# 5V_BUCK.net
KiCad netlist of a schematic drawn in Altium Designer
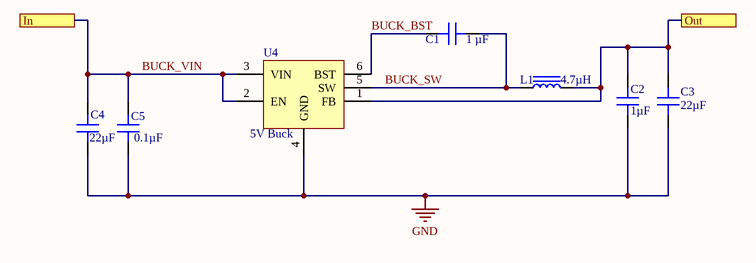
[diagram p0: 5V_BUCK.SchDoc]

(export (version "E")
  (design (tool "Eeschema 10.0.6"))
  (components
    (comp (ref "C1")
      (value "1 µF")
      (footprint "CAP 0402_1005")
      (description "CAP CER 0.1UF 16V X7R 0402")
      (fields (field (name "PART NUMBER") "C0402C104K4RACAUTO") (field (name "MANUFACTURER") "KEMET"))
      (libsource (lib "Celestial Altium Library - altium_library") (part "Capacitor"))
    )
    (comp (ref "C2")
      (value "1µF")
      (footprint "CAP 0603_1608")
      (description "CAP CER 1UF 25V X7R 0603")
      (fields
        (field (name "PART NUMBER") "GCJ188R71E105KA01D")
        (field (name "MANUFACTURER") "Murata Electronics")
      )
      (libsource (lib "Celestial Altium Library - altium_library") (part "Capacitor"))
    )
    (comp (ref "C3")
      (value "22µF")
      (footprint "CAP 0805_2012")
      (description "CAP CER 22UF 16V X5R 0805")
      (fields
        (field (name "PART NUMBER") "CL21A226MOQNNNE")
        (field (name "MANUFACTURER") "Samsung Electro-Mechanics")
      )
      (libsource (lib "Celestial Altium Library - altium_library") (part "Capacitor"))
    )
    (comp (ref "C4")
      (value "22µF")
      (footprint "CAP 0805_2012")
      (description "CAP CER 10UF 25V X7S 0805")
      (fields
        (field (name "PART NUMBER") "C2012X7S1E106K125AC")
        (field (name "MANUFACTURER") "TDK Corporation")
      )
      (libsource (lib "Celestial Altium Library - altium_library") (part "Capacitor"))
    )
    (comp (ref "C5")
      (value "0.1µF")
      (footprint "CAP 0603_1608")
      (description "CAP CER 0.1UF 100V 0603 EPOXY")
      (fields
        (field (name "PART NUMBER") "GCG188R92A104KA03D")
        (field (name "MANUFACTURER") "Murata Electronics")
      )
      (libsource (lib "Celestial Altium Library - altium_library") (part "Capacitor"))
    )
    (comp (ref "L1")
      (value "4.7µH")
      (footprint "IND 1008_2520")
      (description "FIXED IND 4.7UH 1A 110 MOHM SMD")
      (fields (field (name "PART NUMBER") "MLP2520S4R7ST0S1") (field (name "MANUFACTURER") "TDK Corporation"))
      (libsource (lib "Celestial Altium Library - altium_library") (part "Inductor"))
    )
    (comp (ref "U4")
      (value "5V Buck")
      (footprint "TSOT-26-6 - 3.2mm")
      (description "5V fixed step down Buck")
      (libsource (lib "IC") (part "AP63205WU-7"))
    )
  )
  (nets
    (net (code "1") (name "/BUCK_BST") (class "Default")
      (node (ref "C1") (pin "1") (pinfunction "1_1") (pintype "passive"))
      (node (ref "U4") (pin "6") (pinfunction "BST_6") (pintype "passive"))
    )
    (net (code "2") (name "/BUCK_SW") (class "Default")
      (node (ref "C1") (pin "2") (pinfunction "2_2") (pintype "passive"))
      (node (ref "L1") (pin "1") (pinfunction "1_1") (pintype "passive"))
      (node (ref "U4") (pin "5") (pinfunction "SW_5") (pintype "passive"))
    )
    (net (code "3") (name "/BUCK_VIN") (class "Default")
      (node (ref "C4") (pin "2") (pinfunction "2_2") (pintype "passive"))
      (node (ref "C5") (pin "1") (pinfunction "1_1") (pintype "passive"))
      (node (ref "U4") (pin "2") (pinfunction "EN_2") (pintype "passive"))
      (node (ref "U4") (pin "3") (pinfunction "VIN_3") (pintype "passive"))
    )
    (net (code "4") (name "/Out") (class "Default")
      (node (ref "C2") (pin "2") (pinfunction "2_2") (pintype "passive"))
      (node (ref "C3") (pin "2") (pinfunction "2_2") (pintype "passive"))
      (node (ref "L1") (pin "2") (pinfunction "2_2") (pintype "passive"))
      (node (ref "U4") (pin "1") (pinfunction "FB_1") (pintype "passive"))
    )
    (net (code "5") (name "GND") (class "Default")
      (node (ref "C2") (pin "1") (pinfunction "1_1") (pintype "passive"))
      (node (ref "C3") (pin "1") (pinfunction "1_1") (pintype "passive"))
      (node (ref "C4") (pin "1") (pinfunction "1_1") (pintype "passive"))
      (node (ref "C5") (pin "2") (pinfunction "2_2") (pintype "passive"))
      (node (ref "U4") (pin "4") (pinfunction "GND_4") (pintype "passive"))
    )
  )
)
